# 131206_AriloRX_0_0.net
KiCad netlist of a schematic drawn in EAGLE
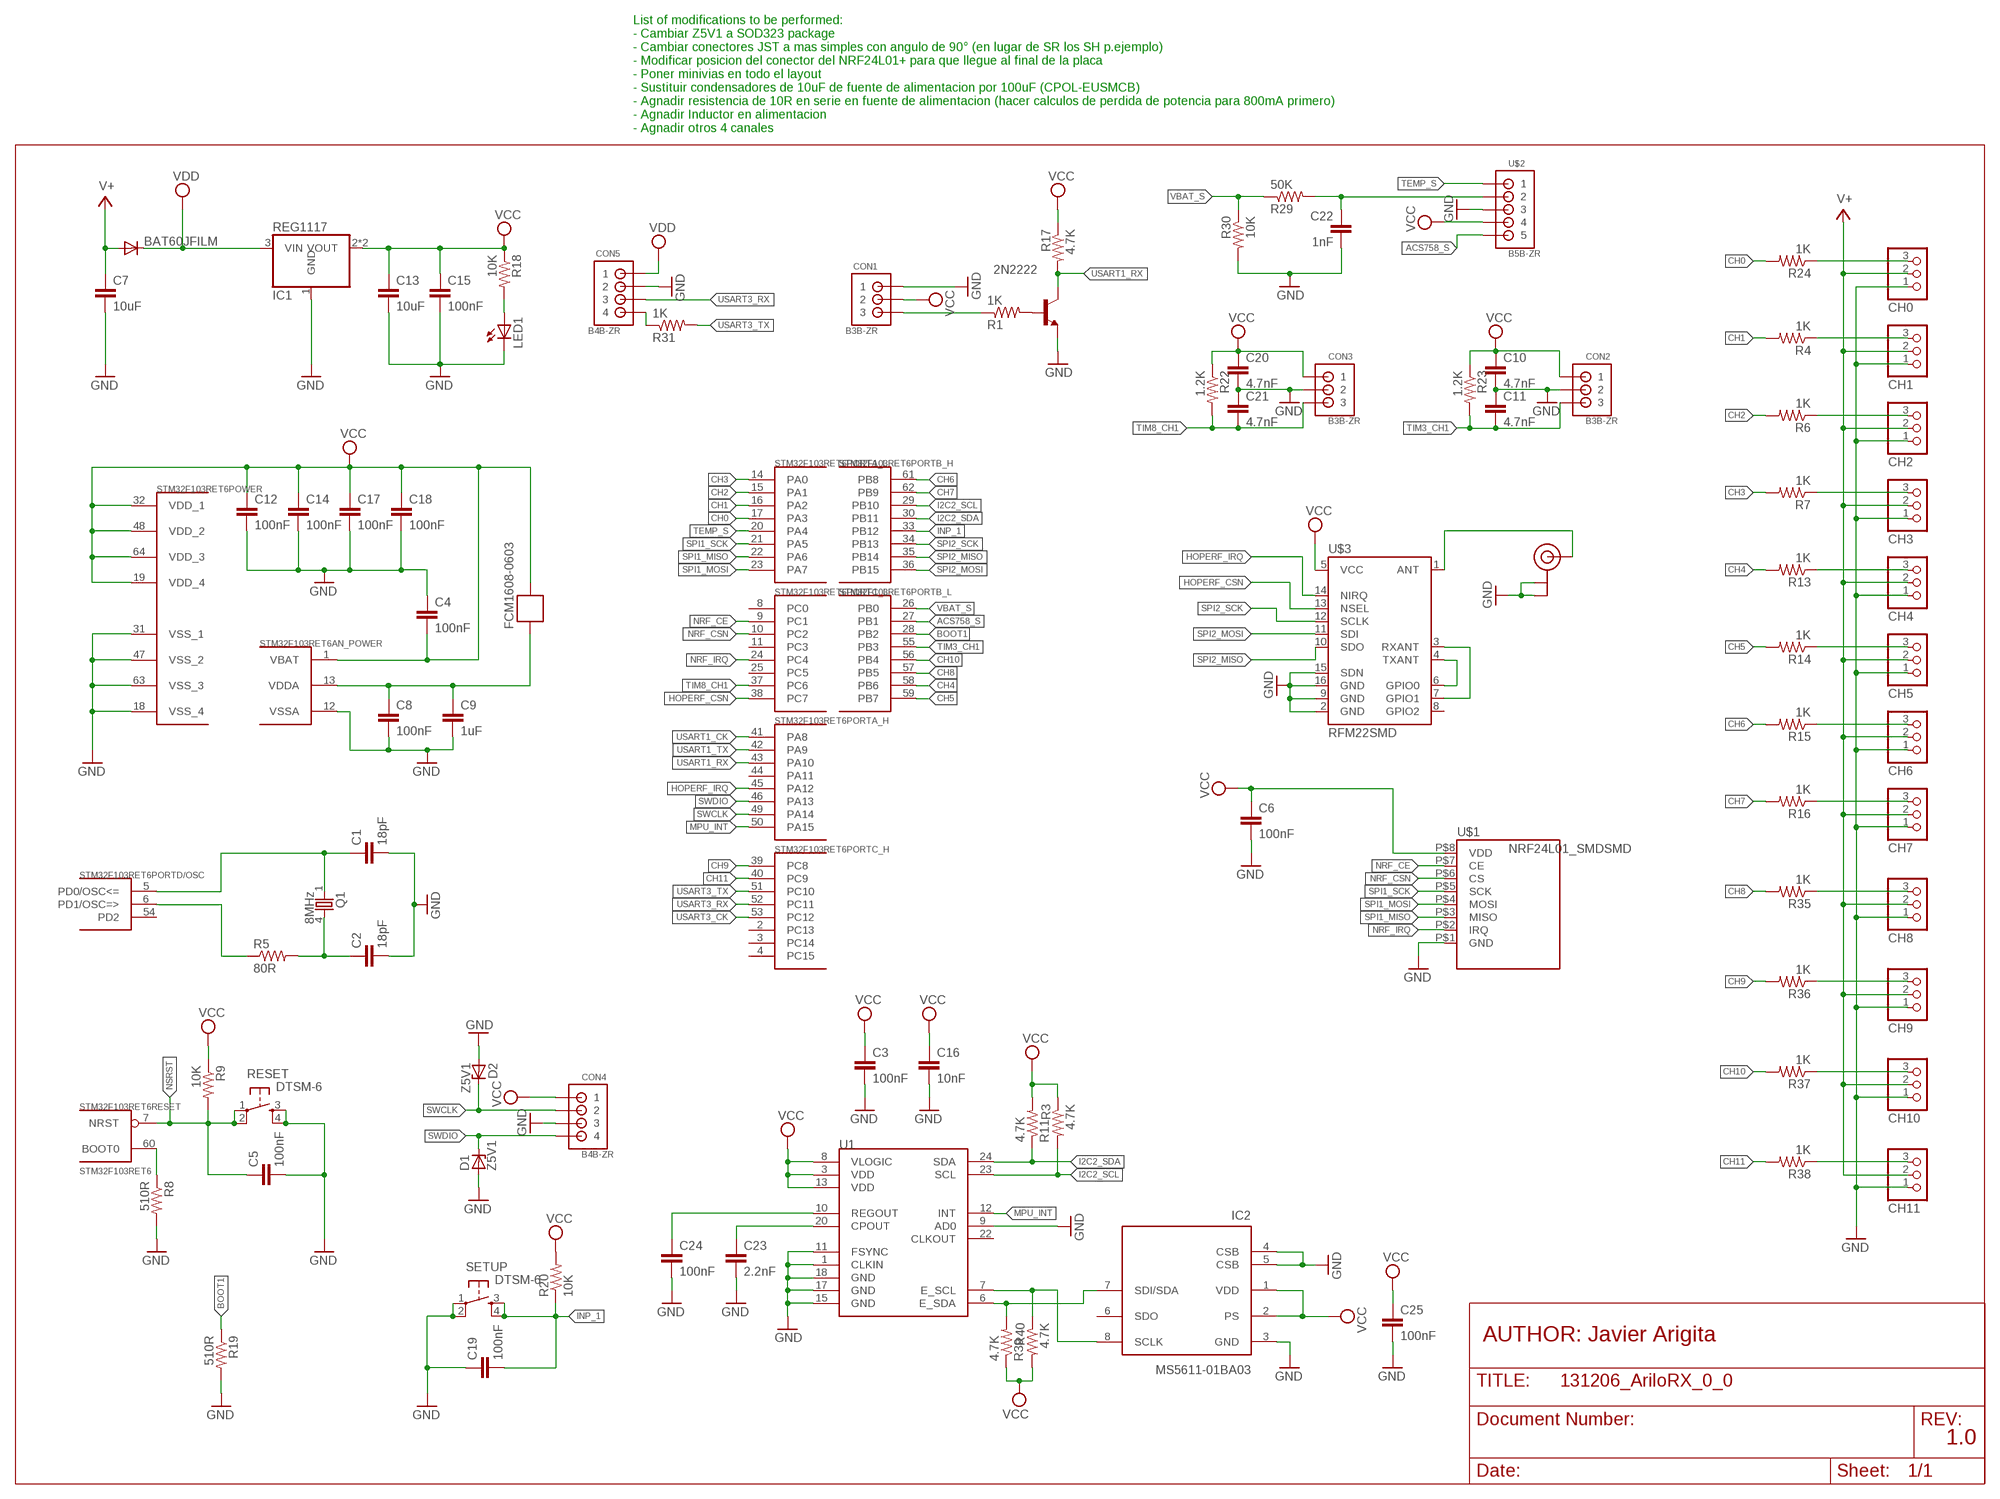
[diagram p0: schematic, sheet 1]

(export (version "E")
  (design (tool "Eeschema 10.0.6"))
  (components
    (comp (ref "2N2222")
      (value "MMBT2222ALT1-NPN-SOT23-BEC")
      (footprint "eagle-import:SOT23-BEC")
      (libsource (lib "eagle-import") (part "-NPN-SOT23-BECMMBT2222ALT1"))
    )
    (comp (ref "BAT60JFILM")
      (value "DIODE-SOD323-R")
      (footprint "eagle-import:SOD323-R")
      (libsource (lib "eagle-import") (part "DIODE-SOD323-R"))
    )
    (comp (ref "C1")
      (value "18pF")
      (footprint "eagle-import:C0805")
      (libsource (lib "eagle-import") (part "C-EUC0805"))
    )
    (comp (ref "C2")
      (value "18pF")
      (footprint "eagle-import:C0805")
      (libsource (lib "eagle-import") (part "C-EUC0805"))
    )
    (comp (ref "C3")
      (value "100nF")
      (footprint "eagle-import:C0805")
      (libsource (lib "eagle-import") (part "C-EUC0805"))
    )
    (comp (ref "C4")
      (value "100nF")
      (footprint "eagle-import:C0805")
      (libsource (lib "eagle-import") (part "C-EUC0805"))
    )
    (comp (ref "C5")
      (value "100nF")
      (footprint "eagle-import:C0805")
      (libsource (lib "eagle-import") (part "C-EUC0805"))
    )
    (comp (ref "C6")
      (value "100nF")
      (footprint "eagle-import:C0805")
      (libsource (lib "eagle-import") (part "C-EUC0805"))
    )
    (comp (ref "C7")
      (value "10uF")
      (footprint "eagle-import:C3216")
      (libsource (lib "eagle-import") (part "resistor_C-EUC3216"))
    )
    (comp (ref "C8")
      (value "100nF")
      (footprint "eagle-import:C0805")
      (libsource (lib "eagle-import") (part "C-EUC0805"))
    )
    (comp (ref "C9")
      (value "1uF")
      (footprint "eagle-import:C3216")
      (libsource (lib "eagle-import") (part "resistor_C-EUC3216"))
    )
    (comp (ref "C10")
      (value "4.7nF")
      (footprint "eagle-import:C0805")
      (libsource (lib "eagle-import") (part "C-EUC0805"))
    )
    (comp (ref "C11")
      (value "4.7nF")
      (footprint "eagle-import:C0805")
      (libsource (lib "eagle-import") (part "C-EUC0805"))
    )
    (comp (ref "C12")
      (value "100nF")
      (footprint "eagle-import:C0805")
      (libsource (lib "eagle-import") (part "C-EUC0805"))
    )
    (comp (ref "C13")
      (value "10uF")
      (footprint "eagle-import:C3216")
      (libsource (lib "eagle-import") (part "resistor_C-EUC3216"))
    )
    (comp (ref "C14")
      (value "100nF")
      (footprint "eagle-import:C0805")
      (libsource (lib "eagle-import") (part "C-EUC0805"))
    )
    (comp (ref "C15")
      (value "100nF")
      (footprint "eagle-import:C0805")
      (libsource (lib "eagle-import") (part "C-EUC0805"))
    )
    (comp (ref "C16")
      (value "10nF")
      (footprint "eagle-import:C0805")
      (libsource (lib "eagle-import") (part "C-EUC0805"))
    )
    (comp (ref "C17")
      (value "100nF")
      (footprint "eagle-import:C0805")
      (libsource (lib "eagle-import") (part "C-EUC0805"))
    )
    (comp (ref "C18")
      (value "100nF")
      (footprint "eagle-import:C0805")
      (libsource (lib "eagle-import") (part "C-EUC0805"))
    )
    (comp (ref "C19")
      (value "100nF")
      (footprint "eagle-import:C0805")
      (libsource (lib "eagle-import") (part "C-EUC0805"))
    )
    (comp (ref "C20")
      (value "4.7nF")
      (footprint "eagle-import:C0805")
      (libsource (lib "eagle-import") (part "C-EUC0805"))
    )
    (comp (ref "C21")
      (value "4.7nF")
      (footprint "eagle-import:C0805")
      (libsource (lib "eagle-import") (part "C-EUC0805"))
    )
    (comp (ref "C22")
      (value "1nF")
      (footprint "eagle-import:C0805")
      (libsource (lib "eagle-import") (part "C-EUC0805"))
    )
    (comp (ref "C23")
      (value "2.2nF")
      (footprint "eagle-import:C0805")
      (libsource (lib "eagle-import") (part "C-EUC0805"))
    )
    (comp (ref "C24")
      (value "100nF")
      (footprint "eagle-import:C0805")
      (libsource (lib "eagle-import") (part "C-EUC0805"))
    )
    (comp (ref "C25")
      (value "100nF")
      (footprint "eagle-import:C0805")
      (libsource (lib "eagle-import") (part "C-EUC0805"))
    )
    (comp (ref "CH0")
      (value "PINHD-1X3")
      (footprint "eagle-import:1X03")
      (libsource (lib "eagle-import") (part "PINHD-1X3"))
    )
    (comp (ref "CH1")
      (value "PINHD-1X3")
      (footprint "eagle-import:1X03")
      (libsource (lib "eagle-import") (part "PINHD-1X3"))
    )
    (comp (ref "CH2")
      (value "PINHD-1X3")
      (footprint "eagle-import:1X03")
      (libsource (lib "eagle-import") (part "PINHD-1X3"))
    )
    (comp (ref "CH3")
      (value "PINHD-1X3")
      (footprint "eagle-import:1X03")
      (libsource (lib "eagle-import") (part "PINHD-1X3"))
    )
    (comp (ref "CH4")
      (value "PINHD-1X3")
      (footprint "eagle-import:1X03")
      (libsource (lib "eagle-import") (part "PINHD-1X3"))
    )
    (comp (ref "CH5")
      (value "PINHD-1X3")
      (footprint "eagle-import:1X03")
      (libsource (lib "eagle-import") (part "PINHD-1X3"))
    )
    (comp (ref "CH6")
      (value "PINHD-1X3")
      (footprint "eagle-import:1X03")
      (libsource (lib "eagle-import") (part "PINHD-1X3"))
    )
    (comp (ref "CH7")
      (value "PINHD-1X3")
      (footprint "eagle-import:1X03")
      (libsource (lib "eagle-import") (part "PINHD-1X3"))
    )
    (comp (ref "CH8")
      (value "PINHD-1X3")
      (footprint "eagle-import:1X03")
      (libsource (lib "eagle-import") (part "PINHD-1X3"))
    )
    (comp (ref "CH9")
      (value "PINHD-1X3")
      (footprint "eagle-import:1X03")
      (libsource (lib "eagle-import") (part "PINHD-1X3"))
    )
    (comp (ref "CH10")
      (value "PINHD-1X3")
      (footprint "eagle-import:1X03")
      (libsource (lib "eagle-import") (part "PINHD-1X3"))
    )
    (comp (ref "CH11")
      (value "PINHD-1X3")
      (footprint "eagle-import:1X03")
      (libsource (lib "eagle-import") (part "PINHD-1X3"))
    )
    (comp (ref "CON1")
      (value "B3B-ZR")
      (footprint "eagle-import:B3B-ZR")
      (libsource (lib "eagle-import") (part "B3B-ZR"))
    )
    (comp (ref "CON2")
      (value "B3B-ZR")
      (footprint "eagle-import:B3B-ZR")
      (libsource (lib "eagle-import") (part "B3B-ZR"))
    )
    (comp (ref "CON3")
      (value "B3B-ZR")
      (footprint "eagle-import:B3B-ZR")
      (libsource (lib "eagle-import") (part "B3B-ZR"))
    )
    (comp (ref "CON4")
      (value "B4B-ZR")
      (footprint "eagle-import:B4B-ZR")
      (libsource (lib "eagle-import") (part "B4B-ZR"))
    )
    (comp (ref "CON5")
      (value "B4B-ZR")
      (footprint "eagle-import:B4B-ZR")
      (libsource (lib "eagle-import") (part "B4B-ZR"))
    )
    (comp (ref "D1")
      (value "Z5V1")
      (footprint "eagle-import:SOD80C")
      (libsource (lib "eagle-import") (part "ZENER-DIODESOD80C"))
    )
    (comp (ref "D2")
      (value "Z5V1")
      (footprint "eagle-import:SOD80C")
      (libsource (lib "eagle-import") (part "ZENER-DIODESOD80C"))
    )
    (comp (ref "FCM1608-0603")
      (value "FERRITE-BEAD")
      (footprint "eagle-import:R0603")
      (libsource (lib "eagle-import") (part "FERRITE-BEAD"))
    )
    (comp (ref "IC1")
      (value "REG1117")
      (footprint "eagle-import:SOT223")
      (libsource (lib "eagle-import") (part "REG1117"))
    )
    (comp (ref "IC2")
      (value "MS5611-01BA03")
      (footprint "eagle-import:SON125P300X500X100-8N")
      (libsource (lib "eagle-import") (part "MS5611-01BA03"))
    )
    (comp (ref "LED1")
      (value "LED0805")
      (footprint "eagle-import:CHIPLED_0805")
      (libsource (lib "eagle-import") (part "LED0805"))
    )
    (comp (ref "Q1")
      (value "8MHz")
      (footprint "eagle-import:MA506")
      (libsource (lib "eagle-import") (part "MA506"))
    )
    (comp (ref "R1")
      (value "1K")
      (footprint "eagle-import:R0805")
      (libsource (lib "eagle-import") (part "RESISTOR0805"))
    )
    (comp (ref "R3")
      (value "4.7K")
      (footprint "eagle-import:R0805")
      (libsource (lib "eagle-import") (part "RESISTOR0805"))
    )
    (comp (ref "R4")
      (value "1K")
      (footprint "eagle-import:R0805")
      (libsource (lib "eagle-import") (part "RESISTOR0805"))
    )
    (comp (ref "R5")
      (value "80R")
      (footprint "eagle-import:R0805")
      (libsource (lib "eagle-import") (part "RESISTOR0805"))
    )
    (comp (ref "R6")
      (value "1K")
      (footprint "eagle-import:R0805")
      (libsource (lib "eagle-import") (part "RESISTOR0805"))
    )
    (comp (ref "R7")
      (value "1K")
      (footprint "eagle-import:R0805")
      (libsource (lib "eagle-import") (part "RESISTOR0805"))
    )
    (comp (ref "R8")
      (value "510R")
      (footprint "eagle-import:R0805")
      (libsource (lib "eagle-import") (part "RESISTOR0805"))
    )
    (comp (ref "R9")
      (value "10K")
      (footprint "eagle-import:R0805")
      (libsource (lib "eagle-import") (part "RESISTOR0805"))
    )
    (comp (ref "R11")
      (value "4.7K")
      (footprint "eagle-import:R0805")
      (libsource (lib "eagle-import") (part "RESISTOR0805"))
    )
    (comp (ref "R13")
      (value "1K")
      (footprint "eagle-import:R0805")
      (libsource (lib "eagle-import") (part "RESISTOR0805"))
    )
    (comp (ref "R14")
      (value "1K")
      (footprint "eagle-import:R0805")
      (libsource (lib "eagle-import") (part "RESISTOR0805"))
    )
    (comp (ref "R15")
      (value "1K")
      (footprint "eagle-import:R0805")
      (libsource (lib "eagle-import") (part "RESISTOR0805"))
    )
    (comp (ref "R16")
      (value "1K")
      (footprint "eagle-import:R0805")
      (libsource (lib "eagle-import") (part "RESISTOR0805"))
    )
    (comp (ref "R17")
      (value "4.7K")
      (footprint "eagle-import:R0805")
      (libsource (lib "eagle-import") (part "RESISTOR0805"))
    )
    (comp (ref "R18")
      (value "10K")
      (footprint "eagle-import:R0805")
      (libsource (lib "eagle-import") (part "RESISTOR0805"))
    )
    (comp (ref "R19")
      (value "510R")
      (footprint "eagle-import:R0805")
      (libsource (lib "eagle-import") (part "RESISTOR0805"))
    )
    (comp (ref "R20")
      (value "10K")
      (footprint "eagle-import:R0805")
      (libsource (lib "eagle-import") (part "RESISTOR0805"))
    )
    (comp (ref "R22")
      (value "1.2K")
      (footprint "eagle-import:R0805")
      (libsource (lib "eagle-import") (part "RESISTOR0805"))
    )
    (comp (ref "R23")
      (value "1.2K")
      (footprint "eagle-import:R0805")
      (libsource (lib "eagle-import") (part "RESISTOR0805"))
    )
    (comp (ref "R24")
      (value "1K")
      (footprint "eagle-import:R0805")
      (libsource (lib "eagle-import") (part "RESISTOR0805"))
    )
    (comp (ref "R29")
      (value "50K")
      (footprint "eagle-import:R0805")
      (libsource (lib "eagle-import") (part "RESISTOR0805"))
    )
    (comp (ref "R30")
      (value "10K")
      (footprint "eagle-import:R0805")
      (libsource (lib "eagle-import") (part "RESISTOR0805"))
    )
    (comp (ref "R31")
      (value "1K")
      (footprint "eagle-import:R0805")
      (libsource (lib "eagle-import") (part "RESISTOR0805"))
    )
    (comp (ref "R35")
      (value "1K")
      (footprint "eagle-import:R0805")
      (libsource (lib "eagle-import") (part "RESISTOR0805"))
    )
    (comp (ref "R36")
      (value "1K")
      (footprint "eagle-import:R0805")
      (libsource (lib "eagle-import") (part "RESISTOR0805"))
    )
    (comp (ref "R37")
      (value "1K")
      (footprint "eagle-import:R0805")
      (libsource (lib "eagle-import") (part "RESISTOR0805"))
    )
    (comp (ref "R38")
      (value "1K")
      (footprint "eagle-import:R0805")
      (libsource (lib "eagle-import") (part "RESISTOR0805"))
    )
    (comp (ref "R39")
      (value "4.7K")
      (footprint "eagle-import:R0805")
      (libsource (lib "eagle-import") (part "RESISTOR0805"))
    )
    (comp (ref "R40")
      (value "4.7K")
      (footprint "eagle-import:R0805")
      (libsource (lib "eagle-import") (part "RESISTOR0805"))
    )
    (comp (ref "RESET")
      (value "DTSM-6")
      (footprint "eagle-import:DTSM-6")
      (libsource (lib "eagle-import") (part "DTSM-6"))
    )
    (comp (ref "SETUP")
      (value "DTSM-6")
      (footprint "eagle-import:DTSM-6")
      (libsource (lib "eagle-import") (part "DTSM-6"))
    )
    (comp (ref "STM32F103RET6")
      (value "STM32F103RET6")
      (footprint "eagle-import:TQFP64")
      (libsource (lib "eagle-import") (part "STM32F10XRXT6"))
    )
    (comp (ref "U$1")
      (value "NRF24L01_SMDSMD")
      (footprint "eagle-import:NRF24L01_SMD")
      (libsource (lib "eagle-import") (part "NRF24L01_SMDSMD"))
    )
    (comp (ref "U$2")
      (value "B5B-ZR")
      (footprint "eagle-import:B5B-ZR")
      (libsource (lib "eagle-import") (part "B5B-ZR"))
    )
    (comp (ref "U$3")
      (value "RFM22SMD")
      (footprint "eagle-import:RFM22-XXX-S2")
      (libsource (lib "eagle-import") (part "RFM22SMD"))
    )
    (comp (ref "U$4")
      (value "U.FL")
      (footprint "eagle-import:U.FL")
      (libsource (lib "eagle-import") (part "U.FL"))
    )
    (comp (ref "U1")
      (value "MPU-9150QFN-24-NP")
      (footprint "eagle-import:QFN-24-NP")
      (libsource (lib "eagle-import") (part "MPU-9150QFN-24-NP"))
    )
  )
  (nets
    (net (code "1") (name "ACS758_S") (class "Default")
      (node (ref "STM32F103RET6") (pin "27") (pinfunction "PB1_27") (pintype "bidirectional"))
      (node (ref "U$2") (pin "5") (pinfunction "5_5") (pintype "bidirectional"))
    )
    (net (code "2") (name "BOOT1") (class "Default")
      (node (ref "R19") (pin "1") (pinfunction "1_1") (pintype "passive"))
      (node (ref "STM32F103RET6") (pin "28") (pinfunction "PB2_28") (pintype "bidirectional"))
    )
    (net (code "3") (name "CH0") (class "Default")
      (node (ref "R24") (pin "2") (pinfunction "2_2") (pintype "passive"))
      (node (ref "STM32F103RET6") (pin "17") (pinfunction "PA3_17") (pintype "bidirectional"))
    )
    (net (code "4") (name "CH1") (class "Default")
      (node (ref "R4") (pin "2") (pinfunction "2_2") (pintype "passive"))
      (node (ref "STM32F103RET6") (pin "16") (pinfunction "PA2_16") (pintype "bidirectional"))
    )
    (net (code "5") (name "CH2") (class "Default")
      (node (ref "R6") (pin "2") (pinfunction "2_2") (pintype "passive"))
      (node (ref "STM32F103RET6") (pin "15") (pinfunction "PA1_15") (pintype "bidirectional"))
    )
    (net (code "6") (name "CH3") (class "Default")
      (node (ref "R7") (pin "2") (pinfunction "2_2") (pintype "passive"))
      (node (ref "STM32F103RET6") (pin "14") (pinfunction "PA0_14") (pintype "bidirectional"))
    )
    (net (code "7") (name "CH4") (class "Default")
      (node (ref "R13") (pin "2") (pinfunction "2_2") (pintype "passive"))
      (node (ref "STM32F103RET6") (pin "58") (pinfunction "PB6_58") (pintype "bidirectional"))
    )
    (net (code "8") (name "CH5") (class "Default")
      (node (ref "R14") (pin "2") (pinfunction "2_2") (pintype "passive"))
      (node (ref "STM32F103RET6") (pin "59") (pinfunction "PB7_59") (pintype "bidirectional"))
    )
    (net (code "9") (name "CH6") (class "Default")
      (node (ref "R15") (pin "2") (pinfunction "2_2") (pintype "passive"))
      (node (ref "STM32F103RET6") (pin "61") (pinfunction "PB8_61") (pintype "bidirectional"))
    )
    (net (code "10") (name "CH7") (class "Default")
      (node (ref "R16") (pin "2") (pinfunction "2_2") (pintype "passive"))
      (node (ref "STM32F103RET6") (pin "62") (pinfunction "PB9_62") (pintype "bidirectional"))
    )
    (net (code "11") (name "CH8") (class "Default")
      (node (ref "R35") (pin "2") (pinfunction "2_2") (pintype "passive"))
      (node (ref "STM32F103RET6") (pin "57") (pinfunction "PB5_57") (pintype "bidirectional"))
    )
    (net (code "12") (name "CH9") (class "Default")
      (node (ref "R36") (pin "2") (pinfunction "2_2") (pintype "passive"))
      (node (ref "STM32F103RET6") (pin "39") (pinfunction "PC8_39") (pintype "bidirectional"))
    )
    (net (code "13") (name "CH10") (class "Default")
      (node (ref "R37") (pin "2") (pinfunction "2_2") (pintype "passive"))
      (node (ref "STM32F103RET6") (pin "56") (pinfunction "PB4_56") (pintype "bidirectional"))
    )
    (net (code "14") (name "CH11") (class "Default")
      (node (ref "R38") (pin "2") (pinfunction "2_2") (pintype "passive"))
      (node (ref "STM32F103RET6") (pin "40") (pinfunction "PC9_40") (pintype "bidirectional"))
    )
    (net (code "15") (name "GND") (class "Default")
      (node (ref "2N2222") (pin "E") (pinfunction "E_E") (pintype "passive"))
      (node (ref "C1") (pin "2") (pinfunction "2_2") (pintype "passive"))
      (node (ref "C10") (pin "2") (pinfunction "2_2") (pintype "passive"))
      (node (ref "C11") (pin "1") (pinfunction "1_1") (pintype "passive"))
      (node (ref "C12") (pin "2") (pinfunction "2_2") (pintype "passive"))
      (node (ref "C13") (pin "2") (pinfunction "2_2") (pintype "passive"))
      (node (ref "C14") (pin "2") (pinfunction "2_2") (pintype "passive"))
      (node (ref "C15") (pin "2") (pinfunction "2_2") (pintype "passive"))
      (node (ref "C16") (pin "2") (pinfunction "2_2") (pintype "passive"))
      (node (ref "C17") (pin "2") (pinfunction "2_2") (pintype "passive"))
      (node (ref "C18") (pin "2") (pinfunction "2_2") (pintype "passive"))
      (node (ref "C19") (pin "1") (pinfunction "1_1") (pintype "passive"))
      (node (ref "C2") (pin "2") (pinfunction "2_2") (pintype "passive"))
      (node (ref "C20") (pin "2") (pinfunction "2_2") (pintype "passive"))
      (node (ref "C21") (pin "1") (pinfunction "1_1") (pintype "passive"))
      (node (ref "C22") (pin "2") (pinfunction "2_2") (pintype "passive"))
      (node (ref "C23") (pin "2") (pinfunction "2_2") (pintype "passive"))
      (node (ref "C24") (pin "2") (pinfunction "2_2") (pintype "passive"))
      (node (ref "C25") (pin "2") (pinfunction "2_2") (pintype "passive"))
      (node (ref "C3") (pin "2") (pinfunction "2_2") (pintype "passive"))
      (node (ref "C4") (pin "1") (pinfunction "1_1") (pintype "passive"))
      (node (ref "C5") (pin "2") (pinfunction "2_2") (pintype "passive"))
      (node (ref "C6") (pin "2") (pinfunction "2_2") (pintype "passive"))
      (node (ref "C7") (pin "2") (pinfunction "2_2") (pintype "passive"))
      (node (ref "C8") (pin "2") (pinfunction "2_2") (pintype "passive"))
      (node (ref "C9") (pin "2") (pinfunction "2_2") (pintype "passive"))
      (node (ref "CH0") (pin "1") (pinfunction "1_1") (pintype "passive"))
      (node (ref "CH1") (pin "1") (pinfunction "1_1") (pintype "passive"))
      (node (ref "CH10") (pin "1") (pinfunction "1_1") (pintype "passive"))
      (node (ref "CH11") (pin "1") (pinfunction "1_1") (pintype "passive"))
      (node (ref "CH2") (pin "1") (pinfunction "1_1") (pintype "passive"))
      (node (ref "CH3") (pin "1") (pinfunction "1_1") (pintype "passive"))
      (node (ref "CH4") (pin "1") (pinfunction "1_1") (pintype "passive"))
      (node (ref "CH5") (pin "1") (pinfunction "1_1") (pintype "passive"))
      (node (ref "CH6") (pin "1") (pinfunction "1_1") (pintype "passive"))
      (node (ref "CH7") (pin "1") (pinfunction "1_1") (pintype "passive"))
      (node (ref "CH8") (pin "1") (pinfunction "1_1") (pintype "passive"))
      (node (ref "CH9") (pin "1") (pinfunction "1_1") (pintype "passive"))
      (node (ref "CON1") (pin "1") (pinfunction "1_1") (pintype "bidirectional"))
      (node (ref "CON2") (pin "2") (pinfunction "2_2") (pintype "bidirectional"))
      (node (ref "CON3") (pin "2") (pinfunction "2_2") (pintype "bidirectional"))
      (node (ref "CON4") (pin "3") (pinfunction "3_3") (pintype "bidirectional"))
      (node (ref "CON5") (pin "2") (pinfunction "2_2") (pintype "bidirectional"))
      (node (ref "D1") (pin "A") (pinfunction "A_A") (pintype "passive"))
      (node (ref "D2") (pin "A") (pinfunction "A_A") (pintype "passive"))
      (node (ref "IC1") (pin "1") (pinfunction "GND_1") (pintype "power_in"))
      (node (ref "IC2") (pin "3") (pinfunction "GND_3") (pintype "power_in"))
      (node (ref "IC2") (pin "4") (pinfunction "CSB_4") (pintype "input"))
      (node (ref "IC2") (pin "5") (pinfunction "CSB_5") (pintype "input"))
      (node (ref "LED1") (pin "C") (pinfunction "C_C") (pintype "passive"))
      (node (ref "R19") (pin "2") (pinfunction "2_2") (pintype "passive"))
      (node (ref "R30") (pin "2") (pinfunction "2_2") (pintype "passive"))
      (node (ref "R8") (pin "2") (pinfunction "2_2") (pintype "passive"))
      (node (ref "RESET") (pin "3") (pinfunction "3_3") (pintype "passive"))
      (node (ref "RESET") (pin "4") (pinfunction "4_4") (pintype "passive"))
      (node (ref "SETUP") (pin "1") (pinfunction "1_1") (pintype "passive"))
      (node (ref "SETUP") (pin "2") (pinfunction "2_2") (pintype "passive"))
      (node (ref "STM32F103RET6") (pin "12") (pinfunction "VSSA_12") (pintype "power_in"))
      (node (ref "STM32F103RET6") (pin "18") (pinfunction "VSS_4_18") (pintype "power_in"))
      (node (ref "STM32F103RET6") (pin "31") (pinfunction "VSS_1_31") (pintype "power_in"))
      (node (ref "STM32F103RET6") (pin "47") (pinfunction "VSS_2_47") (pintype "power_in"))
      (node (ref "STM32F103RET6") (pin "63") (pinfunction "VSS_3_63") (pintype "power_in"))
      (node (ref "U$1") (pin "P$1") (pinfunction "GND_P$1") (pintype "power_in"))
      (node (ref "U$2") (pin "3") (pinfunction "3_3") (pintype "bidirectional"))
      (node (ref "U$3") (pin "15") (pinfunction "SDN_15") (pintype "input"))
      (node (ref "U$3") (pin "16") (pinfunction "GND_16") (pintype "power_in"))
      (node (ref "U$3") (pin "2") (pinfunction "GND_2") (pintype "power_in"))
      (node (ref "U$3") (pin "9") (pinfunction "GND_9") (pintype "power_in"))
      (node (ref "U$4") (pin "P$1") (pinfunction "GND_P$1") (pintype "bidirectional"))
      (node (ref "U$4") (pin "P$2") (pinfunction "GND_P$2") (pintype "bidirectional"))
      (node (ref "U1") (pin "1") (pinfunction "CLKIN_1") (pintype "bidirectional"))
      (node (ref "U1") (pin "11") (pinfunction "FSYNC_11") (pintype "bidirectional"))
      (node (ref "U1") (pin "15") (pinfunction "GND_15") (pintype "bidirectional"))
      (node (ref "U1") (pin "17") (pinfunction "GND_17") (pintype "bidirectional"))
      (node (ref "U1") (pin "18") (pinfunction "GND_18") (pintype "bidirectional"))
      (node (ref "U1") (pin "9") (pinfunction "AD0_9") (pintype "bidirectional"))
    )
    (net (code "16") (name "HOPERF_CSN") (class "Default")
      (node (ref "STM32F103RET6") (pin "38") (pinfunction "PC7_38") (pintype "bidirectional"))
      (node (ref "U$3") (pin "13") (pinfunction "NSEL_13") (pintype "input"))
    )
    (net (code "17") (name "HOPERF_IRQ") (class "Default")
      (node (ref "STM32F103RET6") (pin "45") (pinfunction "PA12_45") (pintype "bidirectional"))
      (node (ref "U$3") (pin "14") (pinfunction "NIRQ_14") (pintype "output"))
    )
    (net (code "18") (name "I2C2_SCL") (class "Default")
      (node (ref "R3") (pin "2") (pinfunction "2_2") (pintype "passive"))
      (node (ref "STM32F103RET6") (pin "29") (pinfunction "PB10_29") (pintype "bidirectional"))
      (node (ref "U1") (pin "23") (pinfunction "SCL_23") (pintype "bidirectional"))
    )
    (net (code "19") (name "I2C2_SDA") (class "Default")
      (node (ref "R11") (pin "1") (pinfunction "1_1") (pintype "passive"))
      (node (ref "STM32F103RET6") (pin "30") (pinfunction "PB11_30") (pintype "bidirectional"))
      (node (ref "U1") (pin "24") (pinfunction "SDA_24") (pintype "bidirectional"))
    )
    (net (code "20") (name "INP_1") (class "Default")
      (node (ref "C19") (pin "2") (pinfunction "2_2") (pintype "passive"))
      (node (ref "R20") (pin "1") (pinfunction "1_1") (pintype "passive"))
      (node (ref "SETUP") (pin "3") (pinfunction "3_3") (pintype "passive"))
      (node (ref "SETUP") (pin "4") (pinfunction "4_4") (pintype "passive"))
      (node (ref "STM32F103RET6") (pin "33") (pinfunction "PB12_33") (pintype "bidirectional"))
    )
    (net (code "21") (name "MPU_INT") (class "Default")
      (node (ref "STM32F103RET6") (pin "50") (pinfunction "PA15_50") (pintype "bidirectional"))
      (node (ref "U1") (pin "12") (pinfunction "INT_12") (pintype "bidirectional"))
    )
    (net (code "22") (name "NRF_CE") (class "Default")
      (node (ref "STM32F103RET6") (pin "9") (pinfunction "PC1_9") (pintype "bidirectional"))
      (node (ref "U$1") (pin "P$7") (pinfunction "CE_P$7") (pintype "input"))
    )
    (net (code "23") (name "NRF_CSN") (class "Default")
      (node (ref "STM32F103RET6") (pin "10") (pinfunction "PC2_10") (pintype "bidirectional"))
      (node (ref "U$1") (pin "P$6") (pinfunction "CS_P$6") (pintype "input"))
    )
    (net (code "24") (name "NRF_IRQ") (class "Default")
      (node (ref "STM32F103RET6") (pin "24") (pinfunction "PC4_24") (pintype "bidirectional"))
      (node (ref "U$1") (pin "P$2") (pinfunction "IRQ_P$2") (pintype "output"))
    )
    (net (code "25") (name "NSRST") (class "Default")
      (node (ref "C5") (pin "1") (pinfunction "1_1") (pintype "passive"))
      (node (ref "R9") (pin "2") (pinfunction "2_2") (pintype "passive"))
      (node (ref "RESET") (pin "1") (pinfunction "1_1") (pintype "passive"))
      (node (ref "RESET") (pin "2") (pinfunction "2_2") (pintype "passive"))
      (node (ref "STM32F103RET6") (pin "7") (pinfunction "NRST_7") (pintype "input"))
    )
    (net (code "26") (name "Net-(2N2222-PadB)") (class "Default")
      (node (ref "2N2222") (pin "B") (pinfunction "B_B") (pintype "passive"))
      (node (ref "R1") (pin "2") (pinfunction "2_2") (pintype "passive"))
    )
    (net (code "27") (name "Net-(C22-Pad1)") (class "Default")
      (node (ref "C22") (pin "1") (pinfunction "1_1") (pintype "passive"))
      (node (ref "R29") (pin "2") (pinfunction "2_2") (pintype "passive"))
      (node (ref "U$2") (pin "2") (pinfunction "2_2") (pintype "bidirectional"))
    )
    (net (code "28") (name "Net-(CH0-Pad3)") (class "Default")
      (node (ref "CH0") (pin "3") (pinfunction "3_3") (pintype "passive"))
      (node (ref "R24") (pin "1") (pinfunction "1_1") (pintype "passive"))
    )
    (net (code "29") (name "Net-(CH1-Pad3)") (class "Default")
      (node (ref "CH1") (pin "3") (pinfunction "3_3") (pintype "passive"))
      (node (ref "R4") (pin "1") (pinfunction "1_1") (pintype "passive"))
    )
    (net (code "30") (name "Net-(CH2-Pad3)") (class "Default")
      (node (ref "CH2") (pin "3") (pinfunction "3_3") (pintype "passive"))
      (node (ref "R6") (pin "1") (pinfunction "1_1") (pintype "passive"))
    )
    (net (code "31") (name "Net-(CH3-Pad3)") (class "Default")
      (node (ref "CH3") (pin "3") (pinfunction "3_3") (pintype "passive"))
      (node (ref "R7") (pin "1") (pinfunction "1_1") (pintype "passive"))
    )
    (net (code "32") (name "Net-(CH4-Pad3)") (class "Default")
      (node (ref "CH4") (pin "3") (pinfunction "3_3") (pintype "passive"))
      (node (ref "R13") (pin "1") (pinfunction "1_1") (pintype "passive"))
    )
    (net (code "33") (name "Net-(CH5-Pad3)") (class "Default")
      (node (ref "CH5") (pin "3") (pinfunction "3_3") (pintype "passive"))
      (node (ref "R14") (pin "1") (pinfunction "1_1") (pintype "passive"))
    )
    (net (code "34") (name "Net-(CH6-Pad3)") (class "Default")
      (node (ref "CH6") (pin "3") (pinfunction "3_3") (pintype "passive"))
      (node (ref "R15") (pin "1") (pinfunction "1_1") (pintype "passive"))
    )
    (net (code "35") (name "Net-(CH7-Pad3)") (class "Default")
      (node (ref "CH7") (pin "3") (pinfunction "3_3") (pintype "passive"))
      (node (ref "R16") (pin "1") (pinfunction "1_1") (pintype "passive"))
    )
    (net (code "36") (name "Net-(CH8-Pad3)") (class "Default")
      (node (ref "CH8") (pin "3") (pinfunction "3_3") (pintype "passive"))
      (node (ref "R35") (pin "1") (pinfunction "1_1") (pintype "passive"))
    )
    (net (code "37") (name "Net-(CH9-Pad3)") (class "Default")
      (node (ref "CH9") (pin "3") (pinfunction "3_3") (pintype "passive"))
      (node (ref "R36") (pin "1") (pinfunction "1_1") (pintype "passive"))
    )
    (net (code "38") (name "Net-(CH10-Pad3)") (class "Default")
      (node (ref "CH10") (pin "3") (pinfunction "3_3") (pintype "passive"))
      (node (ref "R37") (pin "1") (pinfunction "1_1") (pintype "passive"))
    )
    (net (code "39") (name "Net-(CH11-Pad3)") (class "Default")
      (node (ref "CH11") (pin "3") (pinfunction "3_3") (pintype "passive"))
      (node (ref "R38") (pin "1") (pinfunction "1_1") (pintype "passive"))
    )
    (net (code "40") (name "Net-(CON1-Pad3)") (class "Default")
      (node (ref "CON1") (pin "3") (pinfunction "3_3") (pintype "bidirectional"))
      (node (ref "R1") (pin "1") (pinfunction "1_1") (pintype "passive"))
    )
    (net (code "41") (name "Net-(CON5-Pad4)") (class "Default")
      (node (ref "CON5") (pin "4") (pinfunction "4_4") (pintype "bidirectional"))
      (node (ref "R31") (pin "1") (pinfunction "1_1") (pintype "passive"))
    )
    (net (code "42") (name "Net-(FCM1608-0603-P$2)") (class "Default")
      (node (ref "C8") (pin "1") (pinfunction "1_1") (pintype "passive"))
      (node (ref "C9") (pin "1") (pinfunction "1_1") (pintype "passive"))
      (node (ref "FCM1608-0603") (pin "2") (pinfunction "P$2_2") (pintype "bidirectional"))
      (node (ref "STM32F103RET6") (pin "13") (pinfunction "VDDA_13") (pintype "power_in"))
    )
    (net (code "43") (name "Net-(IC2-SCLK)") (class "Default")
      (node (ref "IC2") (pin "8") (pinfunction "SCLK_8") (pintype "input"))
      (node (ref "R40") (pin "1") (pinfunction "1_1") (pintype "passive"))
      (node (ref "U1") (pin "7") (pinfunction "E_SCL_7") (pintype "bidirectional"))
    )
    (net (code "44") (name "Net-(IC2-SDI{slash}SDA)") (class "Default")
      (node (ref "IC2") (pin "7") (pinfunction "SDI/SDA_7") (pintype "bidirectional"))
      (node (ref "R39") (pin "2") (pinfunction "2_2") (pintype "passive"))
      (node (ref "U1") (pin "6") (pinfunction "E_SDA_6") (pintype "bidirectional"))
    )
    (net (code "45") (name "Net-(LED1-PadA)") (class "Default")
      (node (ref "LED1") (pin "A") (pinfunction "A_A") (pintype "passive"))
      (node (ref "R18") (pin "2") (pinfunction "2_2") (pintype "passive"))
    )
    (net (code "46") (name "Net-(Q1-2)") (class "Default")
      (node (ref "C2") (pin "1") (pinfunction "1_1") (pintype "passive"))
      (node (ref "Q1") (pin "4") (pinfunction "2_4") (pintype "passive"))
      (node (ref "R5") (pin "2") (pinfunction "2_2") (pintype "passive"))
    )
    (net (code "47") (name "Net-(STM32F103RET6H-PD0{slash}OSC<=)") (class "Default")
      (node (ref "C1") (pin "1") (pinfunction "1_1") (pintype "passive"))
      (node (ref "Q1") (pin "1") (pinfunction "1_1") (pintype "passive"))
      (node (ref "STM32F103RET6") (pin "5") (pinfunction "PD0/OSC<=_5") (pintype "bidirectional"))
    )
    (net (code "48") (name "Net-(STM32F103RET6H-PD1{slash}OSC=>)") (class "Default")
      (node (ref "R5") (pin "1") (pinfunction "1_1") (pintype "passive"))
      (node (ref "STM32F103RET6") (pin "6") (pinfunction "PD1/OSC=>_6") (pintype "bidirectional"))
    )
    (net (code "49") (name "Net-(STM32F103RET6J-BOOT0)") (class "Default")
      (node (ref "R8") (pin "1") (pinfunction "1_1") (pintype "passive"))
      (node (ref "STM32F103RET6") (pin "60") (pinfunction "BOOT0_60") (pintype "input"))
    )
    (net (code "50") (name "Net-(U$3-ANT)") (class "Default")
      (node (ref "U$3") (pin "1") (pinfunction "ANT_1") (pintype "bidirectional"))
      (node (ref "U$4") (pin "P$3") (pinfunction "SIGNAL_P$3") (pintype "bidirectional"))
    )
    (net (code "51") (name "Net-(U$3-GPIO0)") (class "Default")
      (node (ref "U$3") (pin "4") (pinfunction "TXANT_4") (pintype "input"))
      (node (ref "U$3") (pin "6") (pinfunction "GPIO0_6") (pintype "bidirectional"))
    )
    (net (code "52") (name "Net-(U$3-GPIO1)") (class "Default")
      (node (ref "U$3") (pin "3") (pinfunction "RXANT_3") (pintype "input"))
      (node (ref "U$3") (pin "7") (pinfunction "GPIO1_7") (pintype "bidirectional"))
    )
    (net (code "53") (name "Net-(U1-CPOUT)") (class "Default")
      (node (ref "C23") (pin "1") (pinfunction "1_1") (pintype "passive"))
      (node (ref "U1") (pin "20") (pinfunction "CPOUT_20") (pintype "bidirectional"))
    )
    (net (code "54") (name "Net-(U1-REGOUT)") (class "Default")
      (node (ref "C24") (pin "1") (pinfunction "1_1") (pintype "passive"))
      (node (ref "U1") (pin "10") (pinfunction "REGOUT_10") (pintype "bidirectional"))
    )
    (net (code "55") (name "SPI1_MISO") (class "Default")
      (node (ref "STM32F103RET6") (pin "22") (pinfunction "PA6_22") (pintype "bidirectional"))
      (node (ref "U$1") (pin "P$3") (pinfunction "MISO_P$3") (pintype "output"))
    )
    (net (code "56") (name "SPI1_MOSI") (class "Default")
      (node (ref "STM32F103RET6") (pin "23") (pinfunction "PA7_23") (pintype "bidirectional"))
      (node (ref "U$1") (pin "P$4") (pinfunction "MOSI_P$4") (pintype "input"))
    )
    (net (code "57") (name "SPI1_SCK") (class "Default")
      (node (ref "STM32F103RET6") (pin "21") (pinfunction "PA5_21") (pintype "bidirectional"))
      (node (ref "U$1") (pin "P$5") (pinfunction "SCK_P$5") (pintype "input"))
    )
    (net (code "58") (name "SPI2_MISO") (class "Default")
      (node (ref "STM32F103RET6") (pin "35") (pinfunction "PB14_35") (pintype "bidirectional"))
      (node (ref "U$3") (pin "10") (pinfunction "SDO_10") (pintype "output"))
    )
    (net (code "59") (name "SPI2_MOSI") (class "Default")
      (node (ref "STM32F103RET6") (pin "36") (pinfunction "PB15_36") (pintype "bidirectional"))
      (node (ref "U$3") (pin "11") (pinfunction "SDI_11") (pintype "input"))
    )
    (net (code "60") (name "SPI2_SCK") (class "Default")
      (node (ref "STM32F103RET6") (pin "34") (pinfunction "PB13_34") (pintype "bidirectional"))
      (node (ref "U$3") (pin "12") (pinfunction "SCLK_12") (pintype "input"))
    )
    (net (code "61") (name "SWCLK") (class "Default")
      (node (ref "CON4") (pin "2") (pinfunction "2_2") (pintype "bidirectional"))
      (node (ref "D2") (pin "C") (pinfunction "C_C") (pintype "passive"))
      (node (ref "STM32F103RET6") (pin "49") (pinfunction "PA14_49") (pintype "bidirectional"))
    )
    (net (code "62") (name "SWDIO") (class "Default")
      (node (ref "CON4") (pin "4") (pinfunction "4_4") (pintype "bidirectional"))
      (node (ref "D1") (pin "C") (pinfunction "C_C") (pintype "passive"))
      (node (ref "STM32F103RET6") (pin "46") (pinfunction "PA13_46") (pintype "bidirectional"))
    )
    (net (code "63") (name "TEMP_S") (class "Default")
      (node (ref "STM32F103RET6") (pin "20") (pinfunction "PA4_20") (pintype "bidirectional"))
      (node (ref "U$2") (pin "1") (pinfunction "1_1") (pintype "bidirectional"))
    )
    (net (code "64") (name "TIM3_CH1") (class "Default")
      (node (ref "C11") (pin "2") (pinfunction "2_2") (pintype "passive"))
      (node (ref "CON2") (pin "3") (pinfunction "3_3") (pintype "bidirectional"))
      (node (ref "R23") (pin "2") (pinfunction "2_2") (pintype "passive"))
      (node (ref "STM32F103RET6") (pin "55") (pinfunction "PB3_55") (pintype "bidirectional"))
    )
    (net (code "65") (name "TIM8_CH1") (class "Default")
      (node (ref "C21") (pin "2") (pinfunction "2_2") (pintype "passive"))
      (node (ref "CON3") (pin "3") (pinfunction "3_3") (pintype "bidirectional"))
      (node (ref "R22") (pin "2") (pinfunction "2_2") (pintype "passive"))
      (node (ref "STM32F103RET6") (pin "37") (pinfunction "PC6_37") (pintype "bidirectional"))
    )
    (net (code "66") (name "USART1_CK") (class "Default")
      (node (ref "STM32F103RET6") (pin "41") (pinfunction "PA8_41") (pintype "bidirectional"))
    )
    (net (code "67") (name "USART1_RX") (class "Default")
      (node (ref "2N2222") (pin "C") (pinfunction "C_C") (pintype "passive"))
      (node (ref "R17") (pin "2") (pinfunction "2_2") (pintype "passive"))
      (node (ref "STM32F103RET6") (pin "43") (pinfunction "PA10_43") (pintype "bidirectional"))
    )
    (net (code "68") (name "USART1_TX") (class "Default")
      (node (ref "STM32F103RET6") (pin "42") (pinfunction "PA9_42") (pintype "bidirectional"))
    )
    (net (code "69") (name "USART3_CK") (class "Default")
      (node (ref "STM32F103RET6") (pin "53") (pinfunction "PC12_53") (pintype "bidirectional"))
    )
    (net (code "70") (name "USART3_RX") (class "Default")
      (node (ref "CON5") (pin "3") (pinfunction "3_3") (pintype "bidirectional"))
      (node (ref "STM32F103RET6") (pin "52") (pinfunction "PC11_52") (pintype "bidirectional"))
    )
    (net (code "71") (name "USART3_TX") (class "Default")
      (node (ref "R31") (pin "2") (pinfunction "2_2") (pintype "passive"))
      (node (ref "STM32F103RET6") (pin "51") (pinfunction "PC10_51") (pintype "bidirectional"))
    )
    (net (code "72") (name "V+") (class "Default")
      (node (ref "BAT60JFILM") (pin "A") (pinfunction "A_A") (pintype "passive"))
      (node (ref "C7") (pin "1") (pinfunction "1_1") (pintype "passive"))
      (node (ref "CH0") (pin "2") (pinfunction "2_2") (pintype "passive"))
      (node (ref "CH1") (pin "2") (pinfunction "2_2") (pintype "passive"))
      (node (ref "CH10") (pin "2") (pinfunction "2_2") (pintype "passive"))
      (node (ref "CH11") (pin "2") (pinfunction "2_2") (pintype "passive"))
      (node (ref "CH2") (pin "2") (pinfunction "2_2") (pintype "passive"))
      (node (ref "CH3") (pin "2") (pinfunction "2_2") (pintype "passive"))
      (node (ref "CH4") (pin "2") (pinfunction "2_2") (pintype "passive"))
      (node (ref "CH5") (pin "2") (pinfunction "2_2") (pintype "passive"))
      (node (ref "CH6") (pin "2") (pinfunction "2_2") (pintype "passive"))
      (node (ref "CH7") (pin "2") (pinfunction "2_2") (pintype "passive"))
      (node (ref "CH8") (pin "2") (pinfunction "2_2") (pintype "passive"))
      (node (ref "CH9") (pin "2") (pinfunction "2_2") (pintype "passive"))
    )
    (net (code "73") (name "VBAT_S") (class "Default")
      (node (ref "R29") (pin "1") (pinfunction "1_1") (pintype "passive"))
      (node (ref "R30") (pin "1") (pinfunction "1_1") (pintype "passive"))
      (node (ref "STM32F103RET6") (pin "26") (pinfunction "PB0_26") (pintype "bidirectional"))
    )
    (net (code "74") (name "VCC") (class "Default")
      (node (ref "C10") (pin "1") (pinfunction "1_1") (pintype "passive"))
      (node (ref "C12") (pin "1") (pinfunction "1_1") (pintype "passive"))
      (node (ref "C13") (pin "1") (pinfunction "1_1") (pintype "passive"))
      (node (ref "C14") (pin "1") (pinfunction "1_1") (pintype "passive"))
      (node (ref "C15") (pin "1") (pinfunction "1_1") (pintype "passive"))
      (node (ref "C16") (pin "1") (pinfunction "1_1") (pintype "passive"))
      (node (ref "C17") (pin "1") (pinfunction "1_1") (pintype "passive"))
      (node (ref "C18") (pin "1") (pinfunction "1_1") (pintype "passive"))
      (node (ref "C20") (pin "1") (pinfunction "1_1") (pintype "passive"))
      (node (ref "C25") (pin "1") (pinfunction "1_1") (pintype "passive"))
      (node (ref "C3") (pin "1") (pinfunction "1_1") (pintype "passive"))
      (node (ref "C4") (pin "2") (pinfunction "2_2") (pintype "passive"))
      (node (ref "C6") (pin "1") (pinfunction "1_1") (pintype "passive"))
      (node (ref "CON1") (pin "2") (pinfunction "2_2") (pintype "bidirectional"))
      (node (ref "CON2") (pin "1") (pinfunction "1_1") (pintype "bidirectional"))
      (node (ref "CON3") (pin "1") (pinfunction "1_1") (pintype "bidirectional"))
      (node (ref "CON4") (pin "1") (pinfunction "1_1") (pintype "bidirectional"))
      (node (ref "FCM1608-0603") (pin "1") (pinfunction "P$1_1") (pintype "bidirectional"))
      (node (ref "IC1") (pin "2") (pinfunction "VOUT_2") (pintype "power_in"))
      (node (ref "IC1") (pin "4") (pinfunction "VOUT_4") (pintype "power_in"))
      (node (ref "IC2") (pin "1") (pinfunction "VDD_1") (pintype "power_in"))
      (node (ref "IC2") (pin "2") (pinfunction "PS_2") (pintype "input"))
      (node (ref "R11") (pin "2") (pinfunction "2_2") (pintype "passive"))
      (node (ref "R17") (pin "1") (pinfunction "1_1") (pintype "passive"))
      (node (ref "R18") (pin "1") (pinfunction "1_1") (pintype "passive"))
      (node (ref "R20") (pin "2") (pinfunction "2_2") (pintype "passive"))
      (node (ref "R22") (pin "1") (pinfunction "1_1") (pintype "passive"))
      (node (ref "R23") (pin "1") (pinfunction "1_1") (pintype "passive"))
      (node (ref "R3") (pin "1") (pinfunction "1_1") (pintype "passive"))
      (node (ref "R39") (pin "1") (pinfunction "1_1") (pintype "passive"))
      (node (ref "R40") (pin "2") (pinfunction "2_2") (pintype "passive"))
      (node (ref "R9") (pin "1") (pinfunction "1_1") (pintype "passive"))
      (node (ref "STM32F103RET6") (pin "1") (pinfunction "VBAT_1") (pintype "power_in"))
      (node (ref "STM32F103RET6") (pin "19") (pinfunction "VDD_4_19") (pintype "power_in"))
      (node (ref "STM32F103RET6") (pin "32") (pinfunction "VDD_1_32") (pintype "power_in"))
      (node (ref "STM32F103RET6") (pin "48") (pinfunction "VDD_2_48") (pintype "power_in"))
      (node (ref "STM32F103RET6") (pin "64") (pinfunction "VDD_3_64") (pintype "power_in"))
      (node (ref "U$1") (pin "P$8") (pinfunction "VDD_P$8") (pintype "bidirectional"))
      (node (ref "U$2") (pin "4") (pinfunction "4_4") (pintype "bidirectional"))
      (node (ref "U$3") (pin "5") (pinfunction "VCC_5") (pintype "bidirectional"))
      (node (ref "U1") (pin "13") (pinfunction "VDD_13") (pintype "bidirectional"))
      (node (ref "U1") (pin "3") (pinfunction "VDD_3") (pintype "bidirectional"))
      (node (ref "U1") (pin "8") (pinfunction "VLOGIC_8") (pintype "bidirectional"))
    )
    (net (code "75") (name "VDD") (class "Default")
      (node (ref "BAT60JFILM") (pin "C") (pinfunction "C_C") (pintype "passive"))
      (node (ref "CON5") (pin "1") (pinfunction "1_1") (pintype "bidirectional"))
      (node (ref "IC1") (pin "3") (pinfunction "VIN_3") (pintype "input"))
    )
    (net (code "76") (name "unconnected-(IC2-SDO-Pad6)") (class "Default")
      (node (ref "IC2") (pin "6") (pinfunction "SDO_6") (pintype "output"))
    )
    (net (code "77") (name "unconnected-(STM32F103RET6B-PA11-Pad44)") (class "Default")
      (node (ref "STM32F103RET6") (pin "44") (pinfunction "PA11_44") (pintype "bidirectional"))
    )
    (net (code "78") (name "unconnected-(STM32F103RET6F-PC13-Pad2)") (class "Default")
      (node (ref "STM32F103RET6") (pin "2") (pinfunction "PC13_2") (pintype "bidirectional"))
    )
    (net (code "79") (name "unconnected-(STM32F103RET6F-PC14-Pad3)") (class "Default")
      (node (ref "STM32F103RET6") (pin "3") (pinfunction "PC14_3") (pintype "bidirectional"))
    )
    (net (code "80") (name "unconnected-(STM32F103RET6F-PC15-Pad4)") (class "Default")
      (node (ref "STM32F103RET6") (pin "4") (pinfunction "PC15_4") (pintype "bidirectional"))
    )
    (net (code "81") (name "unconnected-(STM32F103RET6G-PC0-Pad8)") (class "Default")
      (node (ref "STM32F103RET6") (pin "8") (pinfunction "PC0_8") (pintype "bidirectional"))
    )
    (net (code "82") (name "unconnected-(STM32F103RET6G-PC3-Pad11)") (class "Default")
      (node (ref "STM32F103RET6") (pin "11") (pinfunction "PC3_11") (pintype "bidirectional"))
    )
    (net (code "83") (name "unconnected-(STM32F103RET6G-PC5-Pad25)") (class "Default")
      (node (ref "STM32F103RET6") (pin "25") (pinfunction "PC5_25") (pintype "bidirectional"))
    )
    (net (code "84") (name "unconnected-(STM32F103RET6H-PD2-Pad54)") (class "Default")
      (node (ref "STM32F103RET6") (pin "54") (pinfunction "PD2_54") (pintype "bidirectional"))
    )
    (net (code "85") (name "unconnected-(U$3-GPIO2-Pad8)") (class "Default")
      (node (ref "U$3") (pin "8") (pinfunction "GPIO2_8") (pintype "bidirectional"))
    )
    (net (code "86") (name "unconnected-(U1-CLKOUT-Pad22)") (class "Default")
      (node (ref "U1") (pin "22") (pinfunction "CLKOUT_22") (pintype "bidirectional"))
    )
  )
)
